# FPGA_Bank_IO.net
KiCad netlist of a schematic drawn in Altium Designer
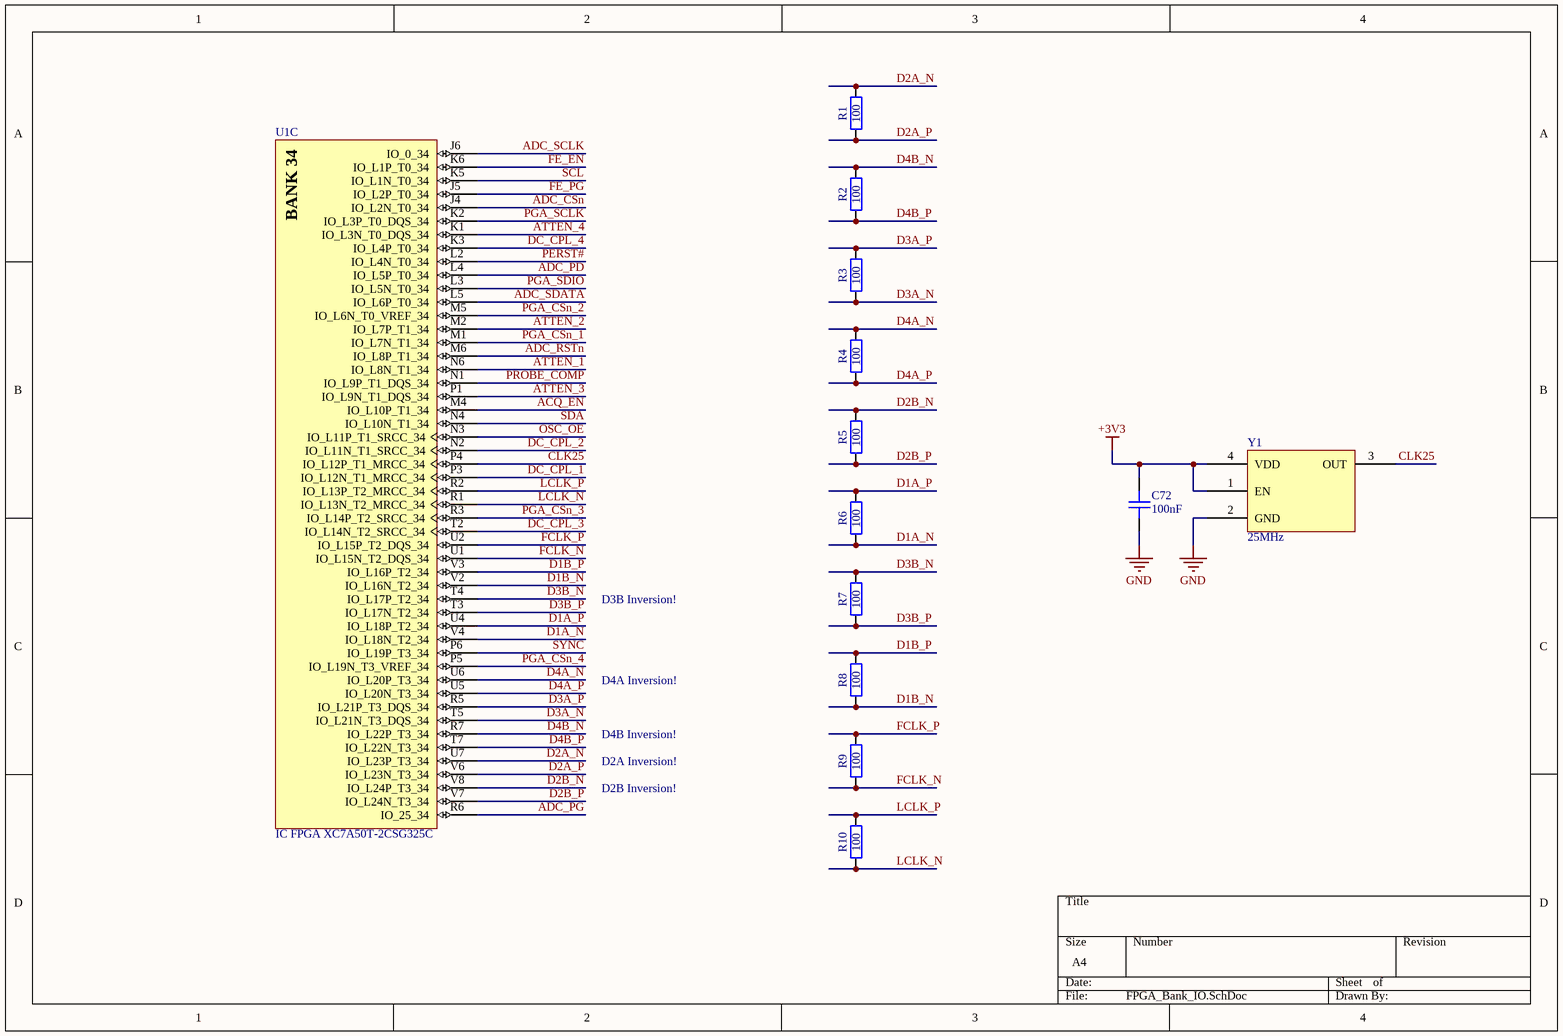
[diagram p0: FPGA_Bank_IO.SchDoc]

(export (version "E")
  (design (tool "Eeschema 10.0.6"))
  (components
    (comp (ref "C72")
      (value "100nF")
      (footprint "GEN_C_0402")
      (libsource (lib "DSO") (part "CAP 100nF 16V X7R 0402"))
    )
    (comp (ref "R1")
      (value "100")
      (footprint "GEN_R_0201")
      (fields (field (name "TOLERANCE") "1%"))
      (libsource (lib "DSO") (part "RES 100 OHM 1% 1/20W 0201"))
    )
    (comp (ref "R2")
      (value "100")
      (footprint "GEN_R_0201")
      (fields (field (name "TOLERANCE") "1%"))
      (libsource (lib "DSO") (part "RES 100 OHM 1% 1/20W 0201"))
    )
    (comp (ref "R3")
      (value "100")
      (footprint "GEN_R_0201")
      (fields (field (name "TOLERANCE") "1%"))
      (libsource (lib "DSO") (part "RES 100 OHM 1% 1/20W 0201"))
    )
    (comp (ref "R4")
      (value "100")
      (footprint "GEN_R_0201")
      (fields (field (name "TOLERANCE") "1%"))
      (libsource (lib "DSO") (part "RES 100 OHM 1% 1/20W 0201"))
    )
    (comp (ref "R5")
      (value "100")
      (footprint "GEN_R_0201")
      (fields (field (name "TOLERANCE") "1%"))
      (libsource (lib "DSO") (part "RES 100 OHM 1% 1/20W 0201"))
    )
    (comp (ref "R6")
      (value "100")
      (footprint "GEN_R_0201")
      (fields (field (name "TOLERANCE") "1%"))
      (libsource (lib "DSO") (part "RES 100 OHM 1% 1/20W 0201"))
    )
    (comp (ref "R7")
      (value "100")
      (footprint "GEN_R_0201")
      (fields (field (name "TOLERANCE") "1%"))
      (libsource (lib "DSO") (part "RES 100 OHM 1% 1/20W 0201"))
    )
    (comp (ref "R8")
      (value "100")
      (footprint "GEN_R_0201")
      (fields (field (name "TOLERANCE") "1%"))
      (libsource (lib "DSO") (part "RES 100 OHM 1% 1/20W 0201"))
    )
    (comp (ref "R9")
      (value "100")
      (footprint "GEN_R_0201")
      (fields (field (name "TOLERANCE") "1%"))
      (libsource (lib "DSO") (part "RES 100 OHM 1% 1/20W 0201"))
    )
    (comp (ref "R10")
      (value "100")
      (footprint "GEN_R_0201")
      (fields (field (name "TOLERANCE") "1%"))
      (libsource (lib "DSO") (part "RES 100 OHM 1% 1/20W 0201"))
    )
    (comp (ref "U1")
      (value "IC FPGA XC7A50T-2CSG325C")
      (footprint "XILINX_XC7A50T-2CSG325C")
      (description "Artix-7 FPGA, 150 User I/Os, 4 GTP, 324-Ball BGA, Speed Grade 2, Commercial Grade, Pb-Free")
      (fields (field (name "MANUFACTURER") "Xilinx") (field (name "PARTNUMBER") "XC7A35T-2CSG325C"))
      (libsource (lib "DSO") (part "IC FPGA XC7A50T-2CSG325C"))
    )
    (comp (ref "Y1")
      (value "25MHz")
      (footprint "ECS_TXO-2016")
      (libsource (lib "DSO") (part "OSC 25MHz ECS-TXO-2016"))
    )
  )
  (nets
    (net (code "1") (name "+3V3") (class "Default")
      (node (ref "C72") (pin "1") (pinfunction "1_1") (pintype "passive"))
      (node (ref "Y1") (pin "1") (pinfunction "EN_1") (pintype "passive"))
      (node (ref "Y1") (pin "4") (pinfunction "VDD_4") (pintype "power_in"))
    )
    (net (code "2") (name "/ACQ_EN") (class "Default")
      (node (ref "U1") (pin "M4") (pinfunction "IO_L10P_T1_34_M4") (pintype "bidirectional"))
    )
    (net (code "3") (name "/ADC_CSn") (class "Default")
      (node (ref "U1") (pin "J4") (pinfunction "IO_L2N_T0_34_J4") (pintype "bidirectional"))
    )
    (net (code "4") (name "/ADC_PD") (class "Default")
      (node (ref "U1") (pin "L4") (pinfunction "IO_L5P_T0_34_L4") (pintype "bidirectional"))
    )
    (net (code "5") (name "/ADC_PG") (class "Default")
      (node (ref "U1") (pin "R6") (pinfunction "IO_25_34_R6") (pintype "bidirectional"))
    )
    (net (code "6") (name "/ADC_RSTn") (class "Default")
      (node (ref "U1") (pin "M6") (pinfunction "IO_L8P_T1_34_M6") (pintype "bidirectional"))
    )
    (net (code "7") (name "/ADC_SCLK") (class "Default")
      (node (ref "U1") (pin "J6") (pinfunction "IO_0_34_J6") (pintype "bidirectional"))
    )
    (net (code "8") (name "/ADC_SDATA") (class "Default")
      (node (ref "U1") (pin "L5") (pinfunction "IO_L6P_T0_34_L5") (pintype "bidirectional"))
    )
    (net (code "9") (name "/ATTEN_1") (class "Default")
      (node (ref "U1") (pin "N6") (pinfunction "IO_L8N_T1_34_N6") (pintype "bidirectional"))
    )
    (net (code "10") (name "/ATTEN_2") (class "Default")
      (node (ref "U1") (pin "M2") (pinfunction "IO_L7P_T1_34_M2") (pintype "bidirectional"))
    )
    (net (code "11") (name "/ATTEN_3") (class "Default")
      (node (ref "U1") (pin "P1") (pinfunction "IO_L9N_T1_DQS_34_P1") (pintype "bidirectional"))
    )
    (net (code "12") (name "/ATTEN_4") (class "Default")
      (node (ref "U1") (pin "K1") (pinfunction "IO_L3N_T0_DQS_34_K1") (pintype "bidirectional"))
    )
    (net (code "13") (name "/CLK25") (class "Default")
      (node (ref "U1") (pin "P4") (pinfunction "IO_L12P_T1_MRCC_34_P4") (pintype "bidirectional"))
      (node (ref "Y1") (pin "3") (pinfunction "OUT_3") (pintype "passive"))
    )
    (net (code "14") (name "/D1A_N") (class "Default")
      (node (ref "R6") (pin "1") (pinfunction "1_1") (pintype "passive"))
      (node (ref "U1") (pin "V4") (pinfunction "IO_L18N_T2_34_V4") (pintype "bidirectional"))
    )
    (net (code "15") (name "/D1A_P") (class "Default")
      (node (ref "R6") (pin "2") (pinfunction "2_2") (pintype "passive"))
      (node (ref "U1") (pin "U4") (pinfunction "IO_L18P_T2_34_U4") (pintype "bidirectional"))
    )
    (net (code "16") (name "/D1B_N") (class "Default")
      (node (ref "R8") (pin "1") (pinfunction "1_1") (pintype "passive"))
      (node (ref "U1") (pin "V2") (pinfunction "IO_L16N_T2_34_V2") (pintype "bidirectional"))
    )
    (net (code "17") (name "/D1B_P") (class "Default")
      (node (ref "R8") (pin "2") (pinfunction "2_2") (pintype "passive"))
      (node (ref "U1") (pin "V3") (pinfunction "IO_L16P_T2_34_V3") (pintype "bidirectional"))
    )
    (net (code "18") (name "/D2A_N") (class "Default")
      (node (ref "R1") (pin "2") (pinfunction "2_2") (pintype "passive"))
      (node (ref "U1") (pin "U7") (pinfunction "IO_L23P_T3_34_U7") (pintype "bidirectional"))
    )
    (net (code "19") (name "/D2A_P") (class "Default")
      (node (ref "R1") (pin "1") (pinfunction "1_1") (pintype "passive"))
      (node (ref "U1") (pin "V6") (pinfunction "IO_L23N_T3_34_V6") (pintype "bidirectional"))
    )
    (net (code "20") (name "/D2B_N") (class "Default")
      (node (ref "R5") (pin "2") (pinfunction "2_2") (pintype "passive"))
      (node (ref "U1") (pin "V8") (pinfunction "IO_L24P_T3_34_V8") (pintype "bidirectional"))
    )
    (net (code "21") (name "/D2B_P") (class "Default")
      (node (ref "R5") (pin "1") (pinfunction "1_1") (pintype "passive"))
      (node (ref "U1") (pin "V7") (pinfunction "IO_L24N_T3_34_V7") (pintype "bidirectional"))
    )
    (net (code "22") (name "/D3A_N") (class "Default")
      (node (ref "R3") (pin "1") (pinfunction "1_1") (pintype "passive"))
      (node (ref "U1") (pin "T5") (pinfunction "IO_L21N_T3_DQS_34_T5") (pintype "bidirectional"))
    )
    (net (code "23") (name "/D3A_P") (class "Default")
      (node (ref "R3") (pin "2") (pinfunction "2_2") (pintype "passive"))
      (node (ref "U1") (pin "R5") (pinfunction "IO_L21P_T3_DQS_34_R5") (pintype "bidirectional"))
    )
    (net (code "24") (name "/D3B_N") (class "Default")
      (node (ref "R7") (pin "2") (pinfunction "2_2") (pintype "passive"))
      (node (ref "U1") (pin "T4") (pinfunction "IO_L17P_T2_34_T4") (pintype "bidirectional"))
    )
    (net (code "25") (name "/D3B_P") (class "Default")
      (node (ref "R7") (pin "1") (pinfunction "1_1") (pintype "passive"))
      (node (ref "U1") (pin "T3") (pinfunction "IO_L17N_T2_34_T3") (pintype "bidirectional"))
    )
    (net (code "26") (name "/D4A_N") (class "Default")
      (node (ref "R4") (pin "2") (pinfunction "2_2") (pintype "passive"))
      (node (ref "U1") (pin "U6") (pinfunction "IO_L20P_T3_34_U6") (pintype "bidirectional"))
    )
    (net (code "27") (name "/D4A_P") (class "Default")
      (node (ref "R4") (pin "1") (pinfunction "1_1") (pintype "passive"))
      (node (ref "U1") (pin "U5") (pinfunction "IO_L20N_T3_34_U5") (pintype "bidirectional"))
    )
    (net (code "28") (name "/D4B_N") (class "Default")
      (node (ref "R2") (pin "2") (pinfunction "2_2") (pintype "passive"))
      (node (ref "U1") (pin "R7") (pinfunction "IO_L22P_T3_34_R7") (pintype "bidirectional"))
    )
    (net (code "29") (name "/D4B_P") (class "Default")
      (node (ref "R2") (pin "1") (pinfunction "1_1") (pintype "passive"))
      (node (ref "U1") (pin "T7") (pinfunction "IO_L22N_T3_34_T7") (pintype "bidirectional"))
    )
    (net (code "30") (name "/DC_CPL_1") (class "Default")
      (node (ref "U1") (pin "P3") (pinfunction "IO_L12N_T1_MRCC_34_P3") (pintype "bidirectional"))
    )
    (net (code "31") (name "/DC_CPL_2") (class "Default")
      (node (ref "U1") (pin "N2") (pinfunction "IO_L11N_T1_SRCC_34_N2") (pintype "bidirectional"))
    )
    (net (code "32") (name "/DC_CPL_3") (class "Default")
      (node (ref "U1") (pin "T2") (pinfunction "IO_L14N_T2_SRCC_34_T2") (pintype "bidirectional"))
    )
    (net (code "33") (name "/DC_CPL_4") (class "Default")
      (node (ref "U1") (pin "K3") (pinfunction "IO_L4P_T0_34_K3") (pintype "bidirectional"))
    )
    (net (code "34") (name "/FCLK_N") (class "Default")
      (node (ref "R9") (pin "1") (pinfunction "1_1") (pintype "passive"))
      (node (ref "U1") (pin "U1") (pinfunction "IO_L15N_T2_DQS_34_U1") (pintype "bidirectional"))
    )
    (net (code "35") (name "/FCLK_P") (class "Default")
      (node (ref "R9") (pin "2") (pinfunction "2_2") (pintype "passive"))
      (node (ref "U1") (pin "U2") (pinfunction "IO_L15P_T2_DQS_34_U2") (pintype "bidirectional"))
    )
    (net (code "36") (name "/FE_EN") (class "Default")
      (node (ref "U1") (pin "K6") (pinfunction "IO_L1P_T0_34_K6") (pintype "bidirectional"))
    )
    (net (code "37") (name "/FE_PG") (class "Default")
      (node (ref "U1") (pin "J5") (pinfunction "IO_L2P_T0_34_J5") (pintype "bidirectional"))
    )
    (net (code "38") (name "/LCLK_N") (class "Default")
      (node (ref "R10") (pin "1") (pinfunction "1_1") (pintype "passive"))
      (node (ref "U1") (pin "R1") (pinfunction "IO_L13N_T2_MRCC_34_R1") (pintype "bidirectional"))
    )
    (net (code "39") (name "/LCLK_P") (class "Default")
      (node (ref "R10") (pin "2") (pinfunction "2_2") (pintype "passive"))
      (node (ref "U1") (pin "R2") (pinfunction "IO_L13P_T2_MRCC_34_R2") (pintype "bidirectional"))
    )
    (net (code "40") (name "/OSC_OE") (class "Default")
      (node (ref "U1") (pin "N3") (pinfunction "IO_L11P_T1_SRCC_34_N3") (pintype "bidirectional"))
    )
    (net (code "41") (name "/PERST#") (class "Default")
      (node (ref "U1") (pin "L2") (pinfunction "IO_L4N_T0_34_L2") (pintype "bidirectional"))
    )
    (net (code "42") (name "/PGA_CSn_1") (class "Default")
      (node (ref "U1") (pin "M1") (pinfunction "IO_L7N_T1_34_M1") (pintype "bidirectional"))
    )
    (net (code "43") (name "/PGA_CSn_2") (class "Default")
      (node (ref "U1") (pin "M5") (pinfunction "IO_L6N_T0_VREF_34_M5") (pintype "bidirectional"))
    )
    (net (code "44") (name "/PGA_CSn_3") (class "Default")
      (node (ref "U1") (pin "R3") (pinfunction "IO_L14P_T2_SRCC_34_R3") (pintype "bidirectional"))
    )
    (net (code "45") (name "/PGA_CSn_4") (class "Default")
      (node (ref "U1") (pin "P5") (pinfunction "IO_L19N_T3_VREF_34_P5") (pintype "bidirectional"))
    )
    (net (code "46") (name "/PGA_SCLK") (class "Default")
      (node (ref "U1") (pin "K2") (pinfunction "IO_L3P_T0_DQS_34_K2") (pintype "bidirectional"))
    )
    (net (code "47") (name "/PGA_SDIO") (class "Default")
      (node (ref "U1") (pin "L3") (pinfunction "IO_L5N_T0_34_L3") (pintype "bidirectional"))
    )
    (net (code "48") (name "/PROBE_COMP") (class "Default")
      (node (ref "U1") (pin "N1") (pinfunction "IO_L9P_T1_DQS_34_N1") (pintype "bidirectional"))
    )
    (net (code "49") (name "/SCL") (class "Default")
      (node (ref "U1") (pin "K5") (pinfunction "IO_L1N_T0_34_K5") (pintype "bidirectional"))
    )
    (net (code "50") (name "/SDA") (class "Default")
      (node (ref "U1") (pin "N4") (pinfunction "IO_L10N_T1_34_N4") (pintype "bidirectional"))
    )
    (net (code "51") (name "/SYNC") (class "Default")
      (node (ref "U1") (pin "P6") (pinfunction "IO_L19P_T3_34_P6") (pintype "bidirectional"))
    )
    (net (code "52") (name "GND") (class "Default")
      (node (ref "C72") (pin "2") (pinfunction "2_2") (pintype "passive"))
      (node (ref "Y1") (pin "2") (pinfunction "GND_2") (pintype "power_in"))
    )
  )
)
